# ESP_01_5V.net
KiCad netlist of a schematic drawn in EAGLE
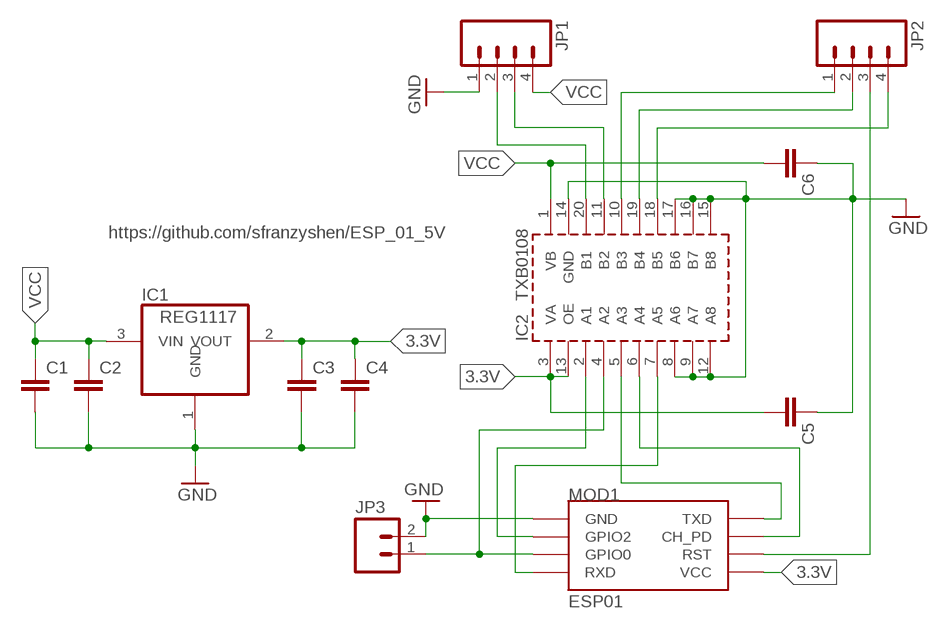
[diagram p0: schematic, sheet 1]

(export (version "E")
  (design (tool "Eeschema 10.0.6"))
  (components
    (comp (ref "C1")
      (value "CAP0603-CAP")
      (footprint "eagle-import:0603-CAP")
      (libsource (lib "eagle-import") (part "CAP0603-CAP"))
    )
    (comp (ref "C2")
      (value "CAP0603-CAP")
      (footprint "eagle-import:0603-CAP")
      (libsource (lib "eagle-import") (part "CAP0603-CAP"))
    )
    (comp (ref "C3")
      (value "CAP0603-CAP")
      (footprint "eagle-import:0603-CAP")
      (libsource (lib "eagle-import") (part "CAP0603-CAP"))
    )
    (comp (ref "C4")
      (value "CAP0603-CAP")
      (footprint "eagle-import:0603-CAP")
      (libsource (lib "eagle-import") (part "CAP0603-CAP"))
    )
    (comp (ref "C5")
      (value "CAP0603-CAP")
      (footprint "eagle-import:0603-CAP")
      (libsource (lib "eagle-import") (part "CAP0603-CAP"))
    )
    (comp (ref "C6")
      (value "CAP0603-CAP")
      (footprint "eagle-import:0603-CAP")
      (libsource (lib "eagle-import") (part "CAP0603-CAP"))
    )
    (comp (ref "IC1")
      (value "REG1117")
      (footprint "eagle-import:SOT223")
      (libsource (lib "eagle-import") (part "REG1117"))
    )
    (comp (ref "IC2")
      (value "IC_TXB0108-TSSOP-20")
      (footprint "eagle-import:TSSOP-20")
      (libsource (lib "eagle-import") (part "IC_TXB0108-TSSOP-20"))
    )
    (comp (ref "JP1")
      (value ".1\" 4 Pin Male")
      (footprint "eagle-import:1X04")
      (libsource (lib "eagle-import") (part "M04PTH"))
    )
    (comp (ref "JP2")
      (value ".1\" 4 Pin Male")
      (footprint "eagle-import:1X04")
      (libsource (lib "eagle-import") (part "M04PTH"))
    )
    (comp (ref "JP3")
      (value "M02PTH")
      (footprint "eagle-import:1X02")
      (libsource (lib "eagle-import") (part "M02PTH"))
    )
    (comp (ref "MOD1")
      (value "ESP01")
      (footprint "eagle-import:ESP01")
      (libsource (lib "eagle-import") (part "ESP01"))
    )
  )
  (nets
    (net (code "1") (name "3.3V") (class "Default")
      (node (ref "C3") (pin "1") (pinfunction "1_1") (pintype "passive"))
      (node (ref "C4") (pin "1") (pinfunction "1_1") (pintype "passive"))
      (node (ref "C5") (pin "2") (pinfunction "2_2") (pintype "passive"))
      (node (ref "IC1") (pin "2") (pinfunction "VOUT_2") (pintype "output"))
      (node (ref "IC2") (pin "13") (pinfunction "OE_13") (pintype "bidirectional"))
      (node (ref "IC2") (pin "3") (pinfunction "VA_3") (pintype "bidirectional"))
      (node (ref "MOD1") (pin "VCC") (pinfunction "VCC_VCC") (pintype "bidirectional"))
    )
    (net (code "2") (name "GND") (class "Default")
      (node (ref "C1") (pin "2") (pinfunction "2_2") (pintype "passive"))
      (node (ref "C2") (pin "2") (pinfunction "2_2") (pintype "passive"))
      (node (ref "C3") (pin "2") (pinfunction "2_2") (pintype "passive"))
      (node (ref "C4") (pin "2") (pinfunction "2_2") (pintype "passive"))
      (node (ref "C5") (pin "1") (pinfunction "1_1") (pintype "passive"))
      (node (ref "C6") (pin "1") (pinfunction "1_1") (pintype "passive"))
      (node (ref "IC1") (pin "1") (pinfunction "GND_1") (pintype "power_in"))
      (node (ref "IC2") (pin "12") (pinfunction "A8_12") (pintype "bidirectional"))
      (node (ref "IC2") (pin "14") (pinfunction "GND_14") (pintype "bidirectional"))
      (node (ref "IC2") (pin "15") (pinfunction "B8_15") (pintype "bidirectional"))
      (node (ref "IC2") (pin "16") (pinfunction "B7_16") (pintype "bidirectional"))
      (node (ref "IC2") (pin "17") (pinfunction "B6_17") (pintype "bidirectional"))
      (node (ref "IC2") (pin "8") (pinfunction "A6_8") (pintype "bidirectional"))
      (node (ref "IC2") (pin "9") (pinfunction "A7_9") (pintype "bidirectional"))
      (node (ref "JP1") (pin "1") (pinfunction "1_1") (pintype "passive"))
      (node (ref "JP3") (pin "2") (pinfunction "2_2") (pintype "passive"))
      (node (ref "MOD1") (pin "GND") (pinfunction "GND_GND") (pintype "bidirectional"))
    )
    (net (code "3") (name "Net-(IC2-A1)") (class "Default")
      (node (ref "IC2") (pin "2") (pinfunction "A1_2") (pintype "bidirectional"))
      (node (ref "MOD1") (pin "GPIO2") (pinfunction "GPIO2_GPIO2") (pintype "bidirectional"))
    )
    (net (code "4") (name "Net-(IC2-A2)") (class "Default")
      (node (ref "IC2") (pin "4") (pinfunction "A2_4") (pintype "bidirectional"))
      (node (ref "JP3") (pin "1") (pinfunction "1_1") (pintype "passive"))
      (node (ref "MOD1") (pin "GPIO0") (pinfunction "GPIO0_GPIO0") (pintype "bidirectional"))
    )
    (net (code "5") (name "Net-(IC2-A3)") (class "Default")
      (node (ref "IC2") (pin "5") (pinfunction "A3_5") (pintype "bidirectional"))
      (node (ref "MOD1") (pin "TX") (pinfunction "TXD_TX") (pintype "bidirectional"))
    )
    (net (code "6") (name "Net-(IC2-A4)") (class "Default")
      (node (ref "IC2") (pin "6") (pinfunction "A4_6") (pintype "bidirectional"))
      (node (ref "MOD1") (pin "CH_PD") (pinfunction "CH_PD_CH_PD") (pintype "bidirectional"))
    )
    (net (code "7") (name "Net-(IC2-A5)") (class "Default")
      (node (ref "IC2") (pin "7") (pinfunction "A5_7") (pintype "bidirectional"))
      (node (ref "MOD1") (pin "RX") (pinfunction "RXD_RX") (pintype "bidirectional"))
    )
    (net (code "8") (name "Net-(IC2-B1)") (class "Default")
      (node (ref "IC2") (pin "20") (pinfunction "B1_20") (pintype "bidirectional"))
      (node (ref "JP1") (pin "2") (pinfunction "2_2") (pintype "passive"))
    )
    (net (code "9") (name "Net-(IC2-B2)") (class "Default")
      (node (ref "IC2") (pin "11") (pinfunction "B2_11") (pintype "bidirectional"))
      (node (ref "JP1") (pin "3") (pinfunction "3_3") (pintype "passive"))
    )
    (net (code "10") (name "Net-(IC2-B3)") (class "Default")
      (node (ref "IC2") (pin "10") (pinfunction "B3_10") (pintype "bidirectional"))
      (node (ref "JP2") (pin "1") (pinfunction "1_1") (pintype "passive"))
    )
    (net (code "11") (name "Net-(IC2-B4)") (class "Default")
      (node (ref "IC2") (pin "19") (pinfunction "B4_19") (pintype "bidirectional"))
      (node (ref "JP2") (pin "2") (pinfunction "2_2") (pintype "passive"))
    )
    (net (code "12") (name "Net-(IC2-B5)") (class "Default")
      (node (ref "IC2") (pin "18") (pinfunction "B5_18") (pintype "bidirectional"))
      (node (ref "JP2") (pin "4") (pinfunction "4_4") (pintype "passive"))
    )
    (net (code "13") (name "Net-(JP2-Pad3)") (class "Default")
      (node (ref "JP2") (pin "3") (pinfunction "3_3") (pintype "passive"))
      (node (ref "MOD1") (pin "RST") (pinfunction "RST_RST") (pintype "bidirectional"))
    )
    (net (code "14") (name "VCC") (class "Default")
      (node (ref "C1") (pin "1") (pinfunction "1_1") (pintype "passive"))
      (node (ref "C2") (pin "1") (pinfunction "1_1") (pintype "passive"))
      (node (ref "C6") (pin "2") (pinfunction "2_2") (pintype "passive"))
      (node (ref "IC1") (pin "3") (pinfunction "VIN_3") (pintype "input"))
      (node (ref "IC2") (pin "1") (pinfunction "VB_1") (pintype "bidirectional"))
      (node (ref "JP1") (pin "4") (pinfunction "4_4") (pintype "passive"))
    )
  )
)
